# iot.net
KiCad netlist of a schematic drawn in Altium Designer
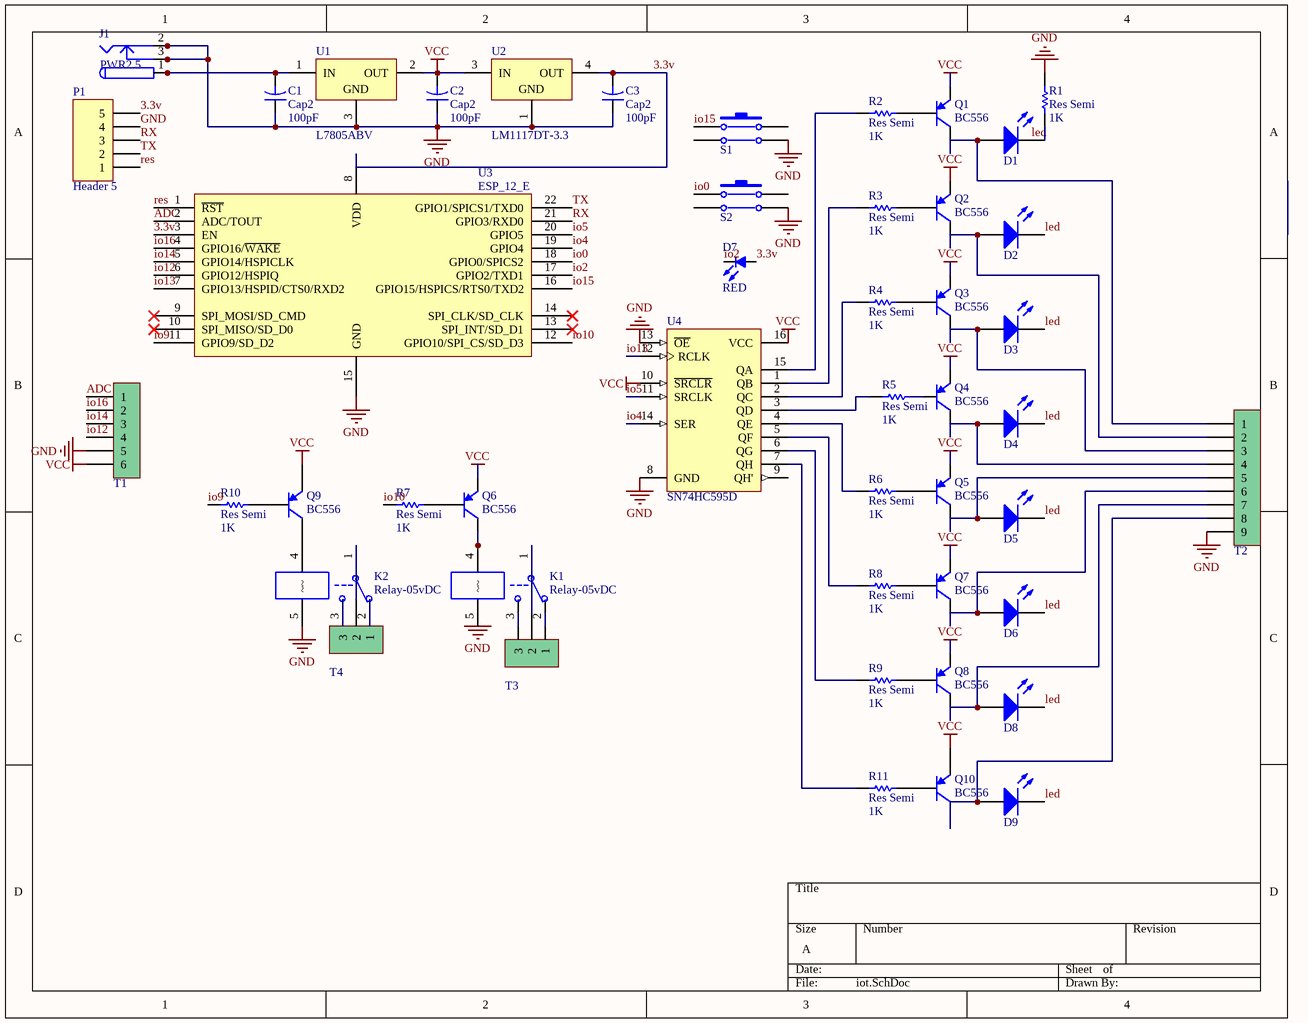
[diagram p0: iot.SchDoc]

(export (version "E")
  (design (tool "Eeschema 10.0.6"))
  (components
    (comp (ref "C1")
      (value "Cap2")
      (footprint "CAPR5-4X5")
      (description "Capacitor")
      (fields (field (name "ALTIUM_VALUE") "100pF") (field (name "PUBLISHER") "Altium Limited"))
      (libsource (lib "Miscellaneous Devices") (part "Cap2"))
    )
    (comp (ref "C2")
      (value "Cap2")
      (footprint "CAPR5-4X5")
      (description "Capacitor")
      (fields (field (name "ALTIUM_VALUE") "100pF") (field (name "PUBLISHER") "Altium Limited"))
      (libsource (lib "Miscellaneous Devices") (part "Cap2"))
    )
    (comp (ref "C3")
      (value "Cap2")
      (footprint "CAPR5-4X5")
      (description "Capacitor")
      (fields (field (name "ALTIUM_VALUE") "100pF") (field (name "PUBLISHER") "Altium Limited"))
      (libsource (lib "Miscellaneous Devices") (part "Cap2"))
    )
    (comp (ref "D1")
      (value "LED 3mm")
      (footprint "LED-3mm")
      (description "Typical LED")
      (fields (field (name "DESIGNER") "Seyed Mohsen Ghasemian") (field (name "PUBLISHER") "www.picpars.com"))
      (libsource (lib "PicPars.com_usefully_Library") (part "LED 3mm"))
    )
    (comp (ref "D2")
      (value "LED 3mm")
      (footprint "LED-3mm")
      (description "Typical LED")
      (fields (field (name "DESIGNER") "Seyed Mohsen Ghasemian") (field (name "PUBLISHER") "www.picpars.com"))
      (libsource (lib "PicPars.com_usefully_Library") (part "LED 3mm"))
    )
    (comp (ref "D3")
      (value "LED 3mm")
      (footprint "LED-3mm")
      (description "Typical LED")
      (fields (field (name "DESIGNER") "Seyed Mohsen Ghasemian") (field (name "PUBLISHER") "www.picpars.com"))
      (libsource (lib "PicPars.com_usefully_Library") (part "LED 3mm"))
    )
    (comp (ref "D4")
      (value "LED 3mm")
      (footprint "LED-3mm")
      (description "Typical LED")
      (fields (field (name "DESIGNER") "Seyed Mohsen Ghasemian") (field (name "PUBLISHER") "www.picpars.com"))
      (libsource (lib "PicPars.com_usefully_Library") (part "LED 3mm"))
    )
    (comp (ref "D5")
      (value "LED 3mm")
      (footprint "LED-3mm")
      (description "Typical LED")
      (fields (field (name "DESIGNER") "Seyed Mohsen Ghasemian") (field (name "PUBLISHER") "www.picpars.com"))
      (libsource (lib "PicPars.com_usefully_Library") (part "LED 3mm"))
    )
    (comp (ref "D6")
      (value "LED 3mm")
      (footprint "LED-3mm")
      (description "Typical LED")
      (fields (field (name "DESIGNER") "Seyed Mohsen Ghasemian") (field (name "PUBLISHER") "www.picpars.com"))
      (libsource (lib "PicPars.com_usefully_Library") (part "LED 3mm"))
    )
    (comp (ref "D7")
      (value "MODEL")
      (footprint "LED-5mm")
      (description "Typical LED")
      (fields (field (name "COLOR") "RED"))
      (libsource (lib "AltiumLib1") (part "LED 5mm"))
    )
    (comp (ref "D8")
      (value "LED 3mm")
      (footprint "LED-3mm")
      (description "Typical LED")
      (fields (field (name "DESIGNER") "Seyed Mohsen Ghasemian") (field (name "PUBLISHER") "www.picpars.com"))
      (libsource (lib "PicPars.com_usefully_Library") (part "LED 3mm"))
    )
    (comp (ref "D9")
      (value "LED 3mm")
      (footprint "LED-3mm")
      (description "Typical LED")
      (fields (field (name "DESIGNER") "Seyed Mohsen Ghasemian") (field (name "PUBLISHER") "www.picpars.com"))
      (libsource (lib "PicPars.com_usefully_Library") (part "LED 3mm"))
    )
    (comp (ref "J1")
      (value "PWR2.5")
      (footprint "KLD-0202")
      (description "Low Voltage Power Supply Connector")
      (fields (field (name "PUBLISHER") "Altium Limited"))
      (libsource (lib "Miscellaneous Connectors") (part "PWR2.5"))
    )
    (comp (ref "K1")
      (value "Relay-05vDC")
      (footprint "Relays")
      (description "Relay-05vDC-240AC 5A")
      (fields (field (name "DESIGNER") "Seyed Mohsen Ghasemain"))
      (libsource (lib "PicPars.com_usefully_Library") (part "Relay-05vDC"))
    )
    (comp (ref "K2")
      (value "Relay-05vDC")
      (footprint "Relays")
      (description "Relay-05vDC-240AC 5A")
      (fields (field (name "DESIGNER") "Seyed Mohsen Ghasemain"))
      (libsource (lib "PicPars.com_usefully_Library") (part "Relay-05vDC"))
    )
    (comp (ref "P1")
      (value "Header 5")
      (footprint "HDR1X5")
      (description "Header, 5-Pin")
      (fields (field (name "PUBLISHER") "Altium Limited"))
      (libsource (lib "Miscellaneous Connectors") (part "Header 5"))
    )
    (comp (ref "Q1")
      (value "BC556")
      (footprint "29-04")
      (description "Amplifier Transistor PNP Silicon")
      (fields (field (name "PUBLISHER") "Altium Limited"))
      (libsource (lib "Motorola Discrete BJT") (part "BC556"))
    )
    (comp (ref "Q2")
      (value "BC556")
      (footprint "29-04")
      (description "Amplifier Transistor PNP Silicon")
      (fields (field (name "PUBLISHER") "Altium Limited"))
      (libsource (lib "Motorola Discrete BJT") (part "BC556"))
    )
    (comp (ref "Q3")
      (value "BC556")
      (footprint "29-04")
      (description "Amplifier Transistor PNP Silicon")
      (fields (field (name "PUBLISHER") "Altium Limited"))
      (libsource (lib "Motorola Discrete BJT") (part "BC556"))
    )
    (comp (ref "Q4")
      (value "BC556")
      (footprint "29-04")
      (description "Amplifier Transistor PNP Silicon")
      (fields (field (name "PUBLISHER") "Altium Limited"))
      (libsource (lib "Motorola Discrete BJT") (part "BC556"))
    )
    (comp (ref "Q5")
      (value "BC556")
      (footprint "29-04")
      (description "Amplifier Transistor PNP Silicon")
      (fields (field (name "PUBLISHER") "Altium Limited"))
      (libsource (lib "Motorola Discrete BJT") (part "BC556"))
    )
    (comp (ref "Q6")
      (value "BC556")
      (footprint "29-04")
      (description "Amplifier Transistor PNP Silicon")
      (fields (field (name "PUBLISHER") "Altium Limited"))
      (libsource (lib "Motorola Discrete BJT") (part "BC556"))
    )
    (comp (ref "Q7")
      (value "BC556")
      (footprint "29-04")
      (description "Amplifier Transistor PNP Silicon")
      (fields (field (name "PUBLISHER") "Altium Limited"))
      (libsource (lib "Motorola Discrete BJT") (part "BC556"))
    )
    (comp (ref "Q8")
      (value "BC556")
      (footprint "29-04")
      (description "Amplifier Transistor PNP Silicon")
      (fields (field (name "PUBLISHER") "Altium Limited"))
      (libsource (lib "Motorola Discrete BJT") (part "BC556"))
    )
    (comp (ref "Q9")
      (value "BC556")
      (footprint "29-04")
      (description "Amplifier Transistor PNP Silicon")
      (fields (field (name "PUBLISHER") "Altium Limited"))
      (libsource (lib "Motorola Discrete BJT") (part "BC556"))
    )
    (comp (ref "Q10")
      (value "BC556")
      (footprint "29-04")
      (description "Amplifier Transistor PNP Silicon")
      (fields (field (name "PUBLISHER") "Altium Limited"))
      (libsource (lib "Motorola Discrete BJT") (part "BC556"))
    )
    (comp (ref "R1")
      (value "Res Semi")
      (footprint "AXIAL-0.5")
      (description "Semiconductor Resistor")
      (fields (field (name "ALTIUM_VALUE") "1K") (field (name "PUBLISHER") "Altium Limited"))
      (libsource (lib "Miscellaneous Devices") (part "Res Semi"))
    )
    (comp (ref "R2")
      (value "Res Semi")
      (footprint "AXIAL-0.5")
      (description "Semiconductor Resistor")
      (fields (field (name "ALTIUM_VALUE") "1K") (field (name "PUBLISHER") "Altium Limited"))
      (libsource (lib "Miscellaneous Devices") (part "Res Semi"))
    )
    (comp (ref "R3")
      (value "Res Semi")
      (footprint "AXIAL-0.5")
      (description "Semiconductor Resistor")
      (fields (field (name "ALTIUM_VALUE") "1K") (field (name "PUBLISHER") "Altium Limited"))
      (libsource (lib "Miscellaneous Devices") (part "Res Semi"))
    )
    (comp (ref "R4")
      (value "Res Semi")
      (footprint "AXIAL-0.5")
      (description "Semiconductor Resistor")
      (fields (field (name "ALTIUM_VALUE") "1K") (field (name "PUBLISHER") "Altium Limited"))
      (libsource (lib "Miscellaneous Devices") (part "Res Semi"))
    )
    (comp (ref "R5")
      (value "Res Semi")
      (footprint "AXIAL-0.5")
      (description "Semiconductor Resistor")
      (fields (field (name "ALTIUM_VALUE") "1K") (field (name "PUBLISHER") "Altium Limited"))
      (libsource (lib "Miscellaneous Devices") (part "Res Semi"))
    )
    (comp (ref "R6")
      (value "Res Semi")
      (footprint "AXIAL-0.5")
      (description "Semiconductor Resistor")
      (fields (field (name "ALTIUM_VALUE") "1K") (field (name "PUBLISHER") "Altium Limited"))
      (libsource (lib "Miscellaneous Devices") (part "Res Semi"))
    )
    (comp (ref "R7")
      (value "Res Semi")
      (footprint "AXIAL-0.5")
      (description "Semiconductor Resistor")
      (fields (field (name "ALTIUM_VALUE") "1K") (field (name "PUBLISHER") "Altium Limited"))
      (libsource (lib "Miscellaneous Devices") (part "Res Semi"))
    )
    (comp (ref "R8")
      (value "Res Semi")
      (footprint "AXIAL-0.5")
      (description "Semiconductor Resistor")
      (fields (field (name "ALTIUM_VALUE") "1K") (field (name "PUBLISHER") "Altium Limited"))
      (libsource (lib "Miscellaneous Devices") (part "Res Semi"))
    )
    (comp (ref "R9")
      (value "Res Semi")
      (footprint "AXIAL-0.5")
      (description "Semiconductor Resistor")
      (fields (field (name "ALTIUM_VALUE") "1K") (field (name "PUBLISHER") "Altium Limited"))
      (libsource (lib "Miscellaneous Devices") (part "Res Semi"))
    )
    (comp (ref "R10")
      (value "Res Semi")
      (footprint "AXIAL-0.5")
      (description "Semiconductor Resistor")
      (fields (field (name "ALTIUM_VALUE") "1K") (field (name "PUBLISHER") "Altium Limited"))
      (libsource (lib "Miscellaneous Devices") (part "Res Semi"))
    )
    (comp (ref "R11")
      (value "Res Semi")
      (footprint "AXIAL-0.5")
      (description "Semiconductor Resistor")
      (fields (field (name "ALTIUM_VALUE") "1K") (field (name "PUBLISHER") "Altium Limited"))
      (libsource (lib "Miscellaneous Devices") (part "Res Semi"))
    )
    (comp (ref "S1")
      (value "PB-4pin")
      (footprint "PB-4pin")
      (description "Switch")
      (fields
        (field (name "PUBLISHER") "www.picpars.com")
        (field (name "E-MAIL") "picpars@gmail.com")
        (field (name "DESIGNER") "Seyed Mohsen Ghasemian")
      )
      (libsource (lib "PicPars.com_usefully_Library") (part "PB-4pin"))
    )
    (comp (ref "S2")
      (value "PB-4pin")
      (footprint "PB-4pin")
      (description "Switch")
      (fields
        (field (name "PUBLISHER") "www.picpars.com")
        (field (name "E-MAIL") "picpars@gmail.com")
        (field (name "DESIGNER") "Seyed Mohsen Ghasemian")
      )
      (libsource (lib "PicPars.com_usefully_Library") (part "PB-4pin"))
    )
    (comp (ref "T1")
      (value "Phoenix terminal")
      (footprint "phoenix terminal 6")
      (description "Terminal 6 Pin")
      (fields (field (name "DESIGNER") "Seyed Mohsen Ghasemain") (field (name "E-MAIL") "picpars@gmail.com"))
      (libsource (lib "PicPars.com_usefully_Library") (part "Phoenix terminal 6"))
    )
    (comp (ref "T2")
      (value "Phoenix terminal")
      (footprint "phoenix terminal 9")
      (description "Terminal 9 Pin")
      (fields (field (name "DESIGNER") "Seyed Mohsen Ghasemain") (field (name "E-MAIL") "picpars@gmail.com"))
      (libsource (lib "PicPars.com_usefully_Library") (part "Phoenix terminal 9"))
    )
    (comp (ref "T3")
      (value "Phoenix terminal")
      (footprint "phoenix terminal 3")
      (description "Terminal 3 Pin")
      (fields (field (name "DESIGNER") "Seyed Mohsen Ghasemain") (field (name "E-MAIL") "picpars@gmail.com"))
      (libsource (lib "PicPars.com_usefully_Library") (part "Phoenix terminal 3"))
    )
    (comp (ref "T4")
      (value "Phoenix terminal")
      (footprint "phoenix terminal 3")
      (description "Terminal 3 Pin")
      (fields (field (name "DESIGNER") "Seyed Mohsen Ghasemain") (field (name "E-MAIL") "picpars@gmail.com"))
      (libsource (lib "PicPars.com_usefully_Library") (part "Phoenix terminal 3"))
    )
    (comp (ref "U1")
      (value "L7805ABV")
      (footprint "TO220ABN")
      (description "Precision 1A Regulator")
      (fields (field (name "PUBLISHER") "Altium Limited"))
      (libsource (lib "ST Power Mgt Voltage Regulator") (part "L7805ABV"))
    )
    (comp (ref "U2")
      (value "LM1117DT-3.3")
      (footprint "TD03B_N")
      (description "800mA Low-Dropout Linear Regulator")
      (fields
        (field (name "MANUFACTURER") "National Semiconductor")
        (field (name "DIGIKEYPARTNUMBER") "LM1117DT-3.3-ND")
        (field (name "PUBLISHER") "Altium Limited")
      )
      (libsource (lib "NSC LDO") (part "LM1117DT-3.3"))
    )
    (comp (ref "U3")
      (value "ESP_12_E")
      (footprint "ESP_12_E")
      (description "ESP-12 Wi-Fi Module by AI-Thinker")
      (libsource (lib "ESP8266") (part "ESP_12_E"))
    )
    (comp (ref "U4")
      (value "SN74HC595D")
      (footprint "D016_N")
      (description "8-Bit Shift Register with 3-State Output Registers")
      (fields (field (name "PUBLISHER") "Altium Limited"))
      (libsource (lib "TI Logic Register") (part "SN74HC595D"))
    )
  )
  (nets
    (net (code "1") (name "/3.3v") (class "Default")
      (node (ref "C3") (pin "2") (pinfunction "2_2") (pintype "passive"))
      (node (ref "D7") (pin "1") (pinfunction "A_1") (pintype "passive"))
      (node (ref "P1") (pin "5") (pinfunction "5_5") (pintype "passive"))
      (node (ref "U2") (pin "4") (pinfunction "OUT_4") (pintype "power_in"))
      (node (ref "U3") (pin "3") (pinfunction "EN_3") (pintype "passive"))
      (node (ref "U3") (pin "8") (pinfunction "VDD_8") (pintype "passive"))
    )
    (net (code "2") (name "/ADC") (class "Default")
      (node (ref "T1") (pin "1") (pinfunction "1_1") (pintype "passive"))
      (node (ref "U3") (pin "2") (pinfunction "ADC/TOUT_2") (pintype "passive"))
    )
    (net (code "3") (name "/RX") (class "Default")
      (node (ref "P1") (pin "3") (pinfunction "3_3") (pintype "passive"))
      (node (ref "U3") (pin "21") (pinfunction "GPIO3/RXD0_21") (pintype "passive"))
    )
    (net (code "4") (name "/TX") (class "Default")
      (node (ref "P1") (pin "2") (pinfunction "2_2") (pintype "passive"))
      (node (ref "U3") (pin "22") (pinfunction "GPIO1/SPICS1/TXD0_22") (pintype "passive"))
    )
    (net (code "5") (name "/io0") (class "Default")
      (node (ref "S2") (pin "1") (pinfunction "1_1") (pintype "passive"))
      (node (ref "U3") (pin "18") (pinfunction "GPIO0/SPICS2_18") (pintype "passive"))
    )
    (net (code "6") (name "/io2") (class "Default")
      (node (ref "D7") (pin "2") (pinfunction "K_2") (pintype "passive"))
      (node (ref "U3") (pin "17") (pinfunction "GPIO2/TXD1_17") (pintype "passive"))
    )
    (net (code "7") (name "/io4") (class "Default")
      (node (ref "U3") (pin "19") (pinfunction "GPIO4_19") (pintype "passive"))
      (node (ref "U4") (pin "14") (pinfunction "SER_14") (pintype "input"))
    )
    (net (code "8") (name "/io5") (class "Default")
      (node (ref "U3") (pin "20") (pinfunction "GPIO5_20") (pintype "passive"))
      (node (ref "U4") (pin "11") (pinfunction "SRCLK_11") (pintype "input"))
    )
    (net (code "9") (name "/io9") (class "Default")
      (node (ref "R10") (pin "1") (pinfunction "1_1") (pintype "passive"))
      (node (ref "U3") (pin "11") (pinfunction "GPIO9/SD_D2_11") (pintype "passive"))
    )
    (net (code "10") (name "/io10") (class "Default")
      (node (ref "R7") (pin "1") (pinfunction "1_1") (pintype "passive"))
      (node (ref "U3") (pin "12") (pinfunction "GPIO10/SPI_CS/SD_D3_12") (pintype "passive"))
    )
    (net (code "11") (name "/io12") (class "Default")
      (node (ref "T1") (pin "4") (pinfunction "4_4") (pintype "passive"))
      (node (ref "U3") (pin "6") (pinfunction "GPIO12/HSPIQ_6") (pintype "passive"))
    )
    (net (code "12") (name "/io13") (class "Default")
      (node (ref "U3") (pin "7") (pinfunction "GPIO13/HSPID/CTS0/RXD2_7") (pintype "passive"))
      (node (ref "U4") (pin "12") (pinfunction "RCLK_12") (pintype "input"))
    )
    (net (code "13") (name "/io14") (class "Default")
      (node (ref "T1") (pin "3") (pinfunction "3_3") (pintype "passive"))
      (node (ref "U3") (pin "5") (pinfunction "GPIO14/HSPICLK_5") (pintype "passive"))
    )
    (net (code "14") (name "/io15") (class "Default")
      (node (ref "S1") (pin "1") (pinfunction "1_1") (pintype "passive"))
      (node (ref "U3") (pin "16") (pinfunction "GPIO15/HSPICS/RTS0/TXD2_16") (pintype "passive"))
    )
    (net (code "15") (name "/io16") (class "Default")
      (node (ref "T1") (pin "2") (pinfunction "2_2") (pintype "passive"))
      (node (ref "U3") (pin "4") (pinfunction "GPIO16/~{WAKE}_4") (pintype "passive"))
    )
    (net (code "16") (name "/led") (class "Default")
      (node (ref "D2") (pin "2") (pinfunction "K_2") (pintype "passive"))
      (node (ref "D3") (pin "2") (pinfunction "K_2") (pintype "passive"))
      (node (ref "D4") (pin "2") (pinfunction "K_2") (pintype "passive"))
      (node (ref "D5") (pin "2") (pinfunction "K_2") (pintype "passive"))
      (node (ref "D6") (pin "2") (pinfunction "K_2") (pintype "passive"))
      (node (ref "D8") (pin "2") (pinfunction "K_2") (pintype "passive"))
      (node (ref "D9") (pin "2") (pinfunction "K_2") (pintype "passive"))
    )
    (net (code "17") (name "/res") (class "Default")
      (node (ref "P1") (pin "1") (pinfunction "1_1") (pintype "passive"))
      (node (ref "U3") (pin "1") (pinfunction "~{RST}_1") (pintype "passive"))
    )
    (net (code "18") (name "GND") (class "Default")
      (node (ref "C1") (pin "1") (pinfunction "1_1") (pintype "passive"))
      (node (ref "C2") (pin "1") (pinfunction "1_1") (pintype "passive"))
      (node (ref "C3") (pin "1") (pinfunction "1_1") (pintype "passive"))
      (node (ref "J1") (pin "2") (pinfunction "2_2") (pintype "power_in"))
      (node (ref "J1") (pin "2A") (pinfunction "2A_2A") (pintype "power_in"))
      (node (ref "J1") (pin "2B") (pinfunction "2B_2B") (pintype "power_in"))
      (node (ref "J1") (pin "3") (pinfunction "3_3") (pintype "power_in"))
      (node (ref "J1") (pin "3A") (pinfunction "3A_3A") (pintype "power_in"))
      (node (ref "J1") (pin "3B") (pinfunction "3B_3B") (pintype "power_in"))
      (node (ref "K2") (pin "5") (pinfunction "~_5") (pintype "passive"))
      (node (ref "P1") (pin "4") (pinfunction "4_4") (pintype "passive"))
      (node (ref "R1") (pin "2") (pinfunction "2_2") (pintype "passive"))
      (node (ref "S1") (pin "4") (pinfunction "4_4") (pintype "passive"))
      (node (ref "S2") (pin "4") (pinfunction "4_4") (pintype "passive"))
      (node (ref "T1") (pin "5") (pinfunction "5_5") (pintype "passive"))
      (node (ref "T2") (pin "9") (pinfunction "9_9") (pintype "passive"))
      (node (ref "U1") (pin "3") (pinfunction "GND_3") (pintype "power_in"))
      (node (ref "U2") (pin "1") (pinfunction "GND_1") (pintype "power_in"))
      (node (ref "U3") (pin "15") (pinfunction "GND_15") (pintype "passive"))
      (node (ref "U4") (pin "13") (pinfunction "~{OE}_13") (pintype "input"))
      (node (ref "U4") (pin "8") (pinfunction "GND_8") (pintype "power_in"))
    )
    (net (code "19") (name "Net-(D1-A)") (class "Default")
      (node (ref "D1") (pin "1") (pinfunction "A_1") (pintype "passive"))
      (node (ref "Q1") (pin "1") (pinfunction "C_1") (pintype "passive"))
      (node (ref "T2") (pin "1") (pinfunction "1_1") (pintype "passive"))
    )
    (net (code "20") (name "Net-(D1-K)") (class "Default")
      (node (ref "D1") (pin "2") (pinfunction "K_2") (pintype "passive"))
      (node (ref "R1") (pin "1") (pinfunction "1_1") (pintype "passive"))
    )
    (net (code "21") (name "Net-(D2-A)") (class "Default")
      (node (ref "D2") (pin "1") (pinfunction "A_1") (pintype "passive"))
      (node (ref "Q2") (pin "1") (pinfunction "C_1") (pintype "passive"))
      (node (ref "T2") (pin "2") (pinfunction "2_2") (pintype "passive"))
    )
    (net (code "22") (name "Net-(D3-A)") (class "Default")
      (node (ref "D3") (pin "1") (pinfunction "A_1") (pintype "passive"))
      (node (ref "Q3") (pin "1") (pinfunction "C_1") (pintype "passive"))
      (node (ref "T2") (pin "3") (pinfunction "3_3") (pintype "passive"))
    )
    (net (code "23") (name "Net-(D4-A)") (class "Default")
      (node (ref "D4") (pin "1") (pinfunction "A_1") (pintype "passive"))
      (node (ref "Q4") (pin "1") (pinfunction "C_1") (pintype "passive"))
      (node (ref "T2") (pin "4") (pinfunction "4_4") (pintype "passive"))
    )
    (net (code "24") (name "Net-(D5-A)") (class "Default")
      (node (ref "D5") (pin "1") (pinfunction "A_1") (pintype "passive"))
      (node (ref "Q5") (pin "1") (pinfunction "C_1") (pintype "passive"))
      (node (ref "T2") (pin "5") (pinfunction "5_5") (pintype "passive"))
    )
    (net (code "25") (name "Net-(D6-A)") (class "Default")
      (node (ref "D6") (pin "1") (pinfunction "A_1") (pintype "passive"))
      (node (ref "Q7") (pin "1") (pinfunction "C_1") (pintype "passive"))
      (node (ref "T2") (pin "6") (pinfunction "6_6") (pintype "passive"))
    )
    (net (code "26") (name "Net-(D8-A)") (class "Default")
      (node (ref "D8") (pin "1") (pinfunction "A_1") (pintype "passive"))
      (node (ref "Q8") (pin "1") (pinfunction "C_1") (pintype "passive"))
      (node (ref "T2") (pin "7") (pinfunction "7_7") (pintype "passive"))
    )
    (net (code "27") (name "Net-(D9-A)") (class "Default")
      (node (ref "D9") (pin "1") (pinfunction "A_1") (pintype "passive"))
      (node (ref "Q10") (pin "1") (pinfunction "C_1") (pintype "passive"))
      (node (ref "T2") (pin "8") (pinfunction "8_8") (pintype "passive"))
    )
    (net (code "28") (name "Net-(K1-COM)") (class "Default")
      (node (ref "K1") (pin "1") (pinfunction "COM_1") (pintype "passive"))
      (node (ref "T3") (pin "2") (pinfunction "2_2") (pintype "passive"))
    )
    (net (code "29") (name "Net-(K1-NC)") (class "Default")
      (node (ref "K1") (pin "2") (pinfunction "NC_2") (pintype "passive"))
      (node (ref "T3") (pin "1") (pinfunction "1_1") (pintype "passive"))
    )
    (net (code "30") (name "Net-(K1-NO)") (class "Default")
      (node (ref "K1") (pin "3") (pinfunction "NO_3") (pintype "passive"))
      (node (ref "T3") (pin "3") (pinfunction "3_3") (pintype "passive"))
    )
    (net (code "31") (name "Net-(K2-COM)") (class "Default")
      (node (ref "K2") (pin "1") (pinfunction "COM_1") (pintype "passive"))
      (node (ref "T4") (pin "2") (pinfunction "2_2") (pintype "passive"))
    )
    (net (code "32") (name "Net-(K2-NC)") (class "Default")
      (node (ref "K2") (pin "2") (pinfunction "NC_2") (pintype "passive"))
      (node (ref "T4") (pin "1") (pinfunction "1_1") (pintype "passive"))
    )
    (net (code "33") (name "Net-(K2-NO)") (class "Default")
      (node (ref "K2") (pin "3") (pinfunction "NO_3") (pintype "passive"))
      (node (ref "T4") (pin "3") (pinfunction "3_3") (pintype "passive"))
    )
    (net (code "34") (name "Net-(Q1-B)") (class "Default")
      (node (ref "Q1") (pin "2") (pinfunction "B_2") (pintype "passive"))
      (node (ref "R2") (pin "2") (pinfunction "2_2") (pintype "passive"))
    )
    (net (code "35") (name "Net-(Q2-B)") (class "Default")
      (node (ref "Q2") (pin "2") (pinfunction "B_2") (pintype "passive"))
      (node (ref "R3") (pin "2") (pinfunction "2_2") (pintype "passive"))
    )
    (net (code "36") (name "Net-(Q3-B)") (class "Default")
      (node (ref "Q3") (pin "2") (pinfunction "B_2") (pintype "passive"))
      (node (ref "R4") (pin "2") (pinfunction "2_2") (pintype "passive"))
    )
    (net (code "37") (name "Net-(Q4-B)") (class "Default")
      (node (ref "Q4") (pin "2") (pinfunction "B_2") (pintype "passive"))
      (node (ref "R5") (pin "2") (pinfunction "2_2") (pintype "passive"))
    )
    (net (code "38") (name "Net-(Q5-B)") (class "Default")
      (node (ref "Q5") (pin "2") (pinfunction "B_2") (pintype "passive"))
      (node (ref "R6") (pin "2") (pinfunction "2_2") (pintype "passive"))
    )
    (net (code "39") (name "Net-(Q6-B)") (class "Default")
      (node (ref "Q6") (pin "2") (pinfunction "B_2") (pintype "passive"))
      (node (ref "R7") (pin "2") (pinfunction "2_2") (pintype "passive"))
    )
    (net (code "40") (name "Net-(Q6-C)") (class "Default")
      (node (ref "K1") (pin "4") (pinfunction "~_4") (pintype "passive"))
      (node (ref "Q6") (pin "1") (pinfunction "C_1") (pintype "passive"))
    )
    (net (code "41") (name "Net-(Q7-B)") (class "Default")
      (node (ref "Q7") (pin "2") (pinfunction "B_2") (pintype "passive"))
      (node (ref "R8") (pin "2") (pinfunction "2_2") (pintype "passive"))
    )
    (net (code "42") (name "Net-(Q8-B)") (class "Default")
      (node (ref "Q8") (pin "2") (pinfunction "B_2") (pintype "passive"))
      (node (ref "R9") (pin "2") (pinfunction "2_2") (pintype "passive"))
    )
    (net (code "43") (name "Net-(Q9-B)") (class "Default")
      (node (ref "Q9") (pin "2") (pinfunction "B_2") (pintype "passive"))
      (node (ref "R10") (pin "2") (pinfunction "2_2") (pintype "passive"))
    )
    (net (code "44") (name "Net-(Q9-C)") (class "Default")
      (node (ref "K2") (pin "4") (pinfunction "~_4") (pintype "passive"))
      (node (ref "Q9") (pin "1") (pinfunction "C_1") (pintype "passive"))
    )
    (net (code "45") (name "Net-(Q10-B)") (class "Default")
      (node (ref "Q10") (pin "2") (pinfunction "B_2") (pintype "passive"))
      (node (ref "R11") (pin "2") (pinfunction "2_2") (pintype "passive"))
    )
    (net (code "46") (name "Net-(U1-IN)") (class "Default")
      (node (ref "C1") (pin "2") (pinfunction "2_2") (pintype "passive"))
      (node (ref "J1") (pin "1") (pinfunction "1_1") (pintype "power_in"))
      (node (ref "J1") (pin "1A") (pinfunction "1A_1A") (pintype "power_in"))
      (node (ref "J1") (pin "1B") (pinfunction "1B_1B") (pintype "power_in"))
      (node (ref "U1") (pin "1") (pinfunction "IN_1") (pintype "power_in"))
    )
    (net (code "47") (name "Net-(U4-QA)") (class "Default")
      (node (ref "R2") (pin "1") (pinfunction "1_1") (pintype "passive"))
      (node (ref "U4") (pin "15") (pinfunction "QA_15") (pintype "tri_state"))
    )
    (net (code "48") (name "Net-(U4-QB)") (class "Default")
      (node (ref "R3") (pin "1") (pinfunction "1_1") (pintype "passive"))
      (node (ref "U4") (pin "1") (pinfunction "QB_1") (pintype "tri_state"))
    )
    (net (code "49") (name "Net-(U4-QC)") (class "Default")
      (node (ref "R4") (pin "1") (pinfunction "1_1") (pintype "passive"))
      (node (ref "U4") (pin "2") (pinfunction "QC_2") (pintype "tri_state"))
    )
    (net (code "50") (name "Net-(U4-QD)") (class "Default")
      (node (ref "R5") (pin "1") (pinfunction "1_1") (pintype "passive"))
      (node (ref "U4") (pin "3") (pinfunction "QD_3") (pintype "tri_state"))
    )
    (net (code "51") (name "Net-(U4-QE)") (class "Default")
      (node (ref "R6") (pin "1") (pinfunction "1_1") (pintype "passive"))
      (node (ref "U4") (pin "4") (pinfunction "QE_4") (pintype "tri_state"))
    )
    (net (code "52") (name "Net-(U4-QF)") (class "Default")
      (node (ref "R8") (pin "1") (pinfunction "1_1") (pintype "passive"))
      (node (ref "U4") (pin "5") (pinfunction "QF_5") (pintype "tri_state"))
    )
    (net (code "53") (name "Net-(U4-QG)") (class "Default")
      (node (ref "R9") (pin "1") (pinfunction "1_1") (pintype "passive"))
      (node (ref "U4") (pin "6") (pinfunction "QG_6") (pintype "tri_state"))
    )
    (net (code "54") (name "Net-(U4-QH)") (class "Default")
      (node (ref "R11") (pin "1") (pinfunction "1_1") (pintype "passive"))
      (node (ref "U4") (pin "7") (pinfunction "QH_7") (pintype "tri_state"))
    )
    (net (code "55") (name "VCC") (class "Default")
      (node (ref "C2") (pin "2") (pinfunction "2_2") (pintype "passive"))
      (node (ref "Q1") (pin "3") (pinfunction "E_3") (pintype "passive"))
      (node (ref "Q10") (pin "3") (pinfunction "E_3") (pintype "passive"))
      (node (ref "Q3") (pin "3") (pinfunction "E_3") (pintype "passive"))
      (node (ref "Q4") (pin "3") (pinfunction "E_3") (pintype "passive"))
      (node (ref "Q5") (pin "3") (pinfunction "E_3") (pintype "passive"))
      (node (ref "Q6") (pin "3") (pinfunction "E_3") (pintype "passive"))
      (node (ref "Q7") (pin "3") (pinfunction "E_3") (pintype "passive"))
      (node (ref "Q8") (pin "3") (pinfunction "E_3") (pintype "passive"))
      (node (ref "Q9") (pin "3") (pinfunction "E_3") (pintype "passive"))
      (node (ref "T1") (pin "6") (pinfunction "6_6") (pintype "passive"))
      (node (ref "U1") (pin "2") (pinfunction "OUT_2") (pintype "power_in"))
      (node (ref "U2") (pin "3") (pinfunction "IN_3") (pintype "power_in"))
      (node (ref "U4") (pin "10") (pinfunction "~{SRCLR}_10") (pintype "input"))
      (node (ref "U4") (pin "16") (pinfunction "VCC_16") (pintype "power_in"))
    )
    (net (code "56") (name "unconnected-(K1-~-Pad5)") (class "Default")
      (node (ref "K1") (pin "5") (pinfunction "~_5") (pintype "passive"))
    )
    (net (code "57") (name "unconnected-(Q2-E-Pad3)") (class "Default")
      (node (ref "Q2") (pin "3") (pinfunction "E_3") (pintype "passive"))
    )
    (net (code "58") (name "unconnected-(S1-Pad2)") (class "Default")
      (node (ref "S1") (pin "2") (pinfunction "2_2") (pintype "passive"))
    )
    (net (code "59") (name "unconnected-(S1-Pad3)") (class "Default")
      (node (ref "S1") (pin "3") (pinfunction "3_3") (pintype "passive"))
    )
    (net (code "60") (name "unconnected-(S2-Pad2)") (class "Default")
      (node (ref "S2") (pin "2") (pinfunction "2_2") (pintype "passive"))
    )
    (net (code "61") (name "unconnected-(S2-Pad3)") (class "Default")
      (node (ref "S2") (pin "3") (pinfunction "3_3") (pintype "passive"))
    )
    (net (code "62") (name "unconnected-(U3-SPI_CLK{slash}SD_CLK-Pad14)") (class "Default")
      (node (ref "U3") (pin "14") (pinfunction "SPI_CLK/SD_CLK_14") (pintype "passive+no_connect"))
    )
    (net (code "63") (name "unconnected-(U3-SPI_INT{slash}SD_D1-Pad13)") (class "Default")
      (node (ref "U3") (pin "13") (pinfunction "SPI_INT/SD_D1_13") (pintype "passive+no_connect"))
    )
    (net (code "64") (name "unconnected-(U3-SPI_MISO{slash}SD_D0-Pad10)") (class "Default")
      (node (ref "U3") (pin "10") (pinfunction "SPI_MISO/SD_D0_10") (pintype "passive+no_connect"))
    )
    (net (code "65") (name "unconnected-(U3-SPI_MOSI{slash}SD_CMD-Pad9)") (class "Default")
      (node (ref "U3") (pin "9") (pinfunction "SPI_MOSI/SD_CMD_9") (pintype "passive+no_connect"))
    )
    (net (code "66") (name "unconnected-(U4-QH'-Pad9)") (class "Default")
      (node (ref "U4") (pin "9") (pinfunction "QH'_9") (pintype "output"))
    )
  )
)
